# IO_Supply_Filter.net
KiCad netlist of a schematic drawn in Altium Designer
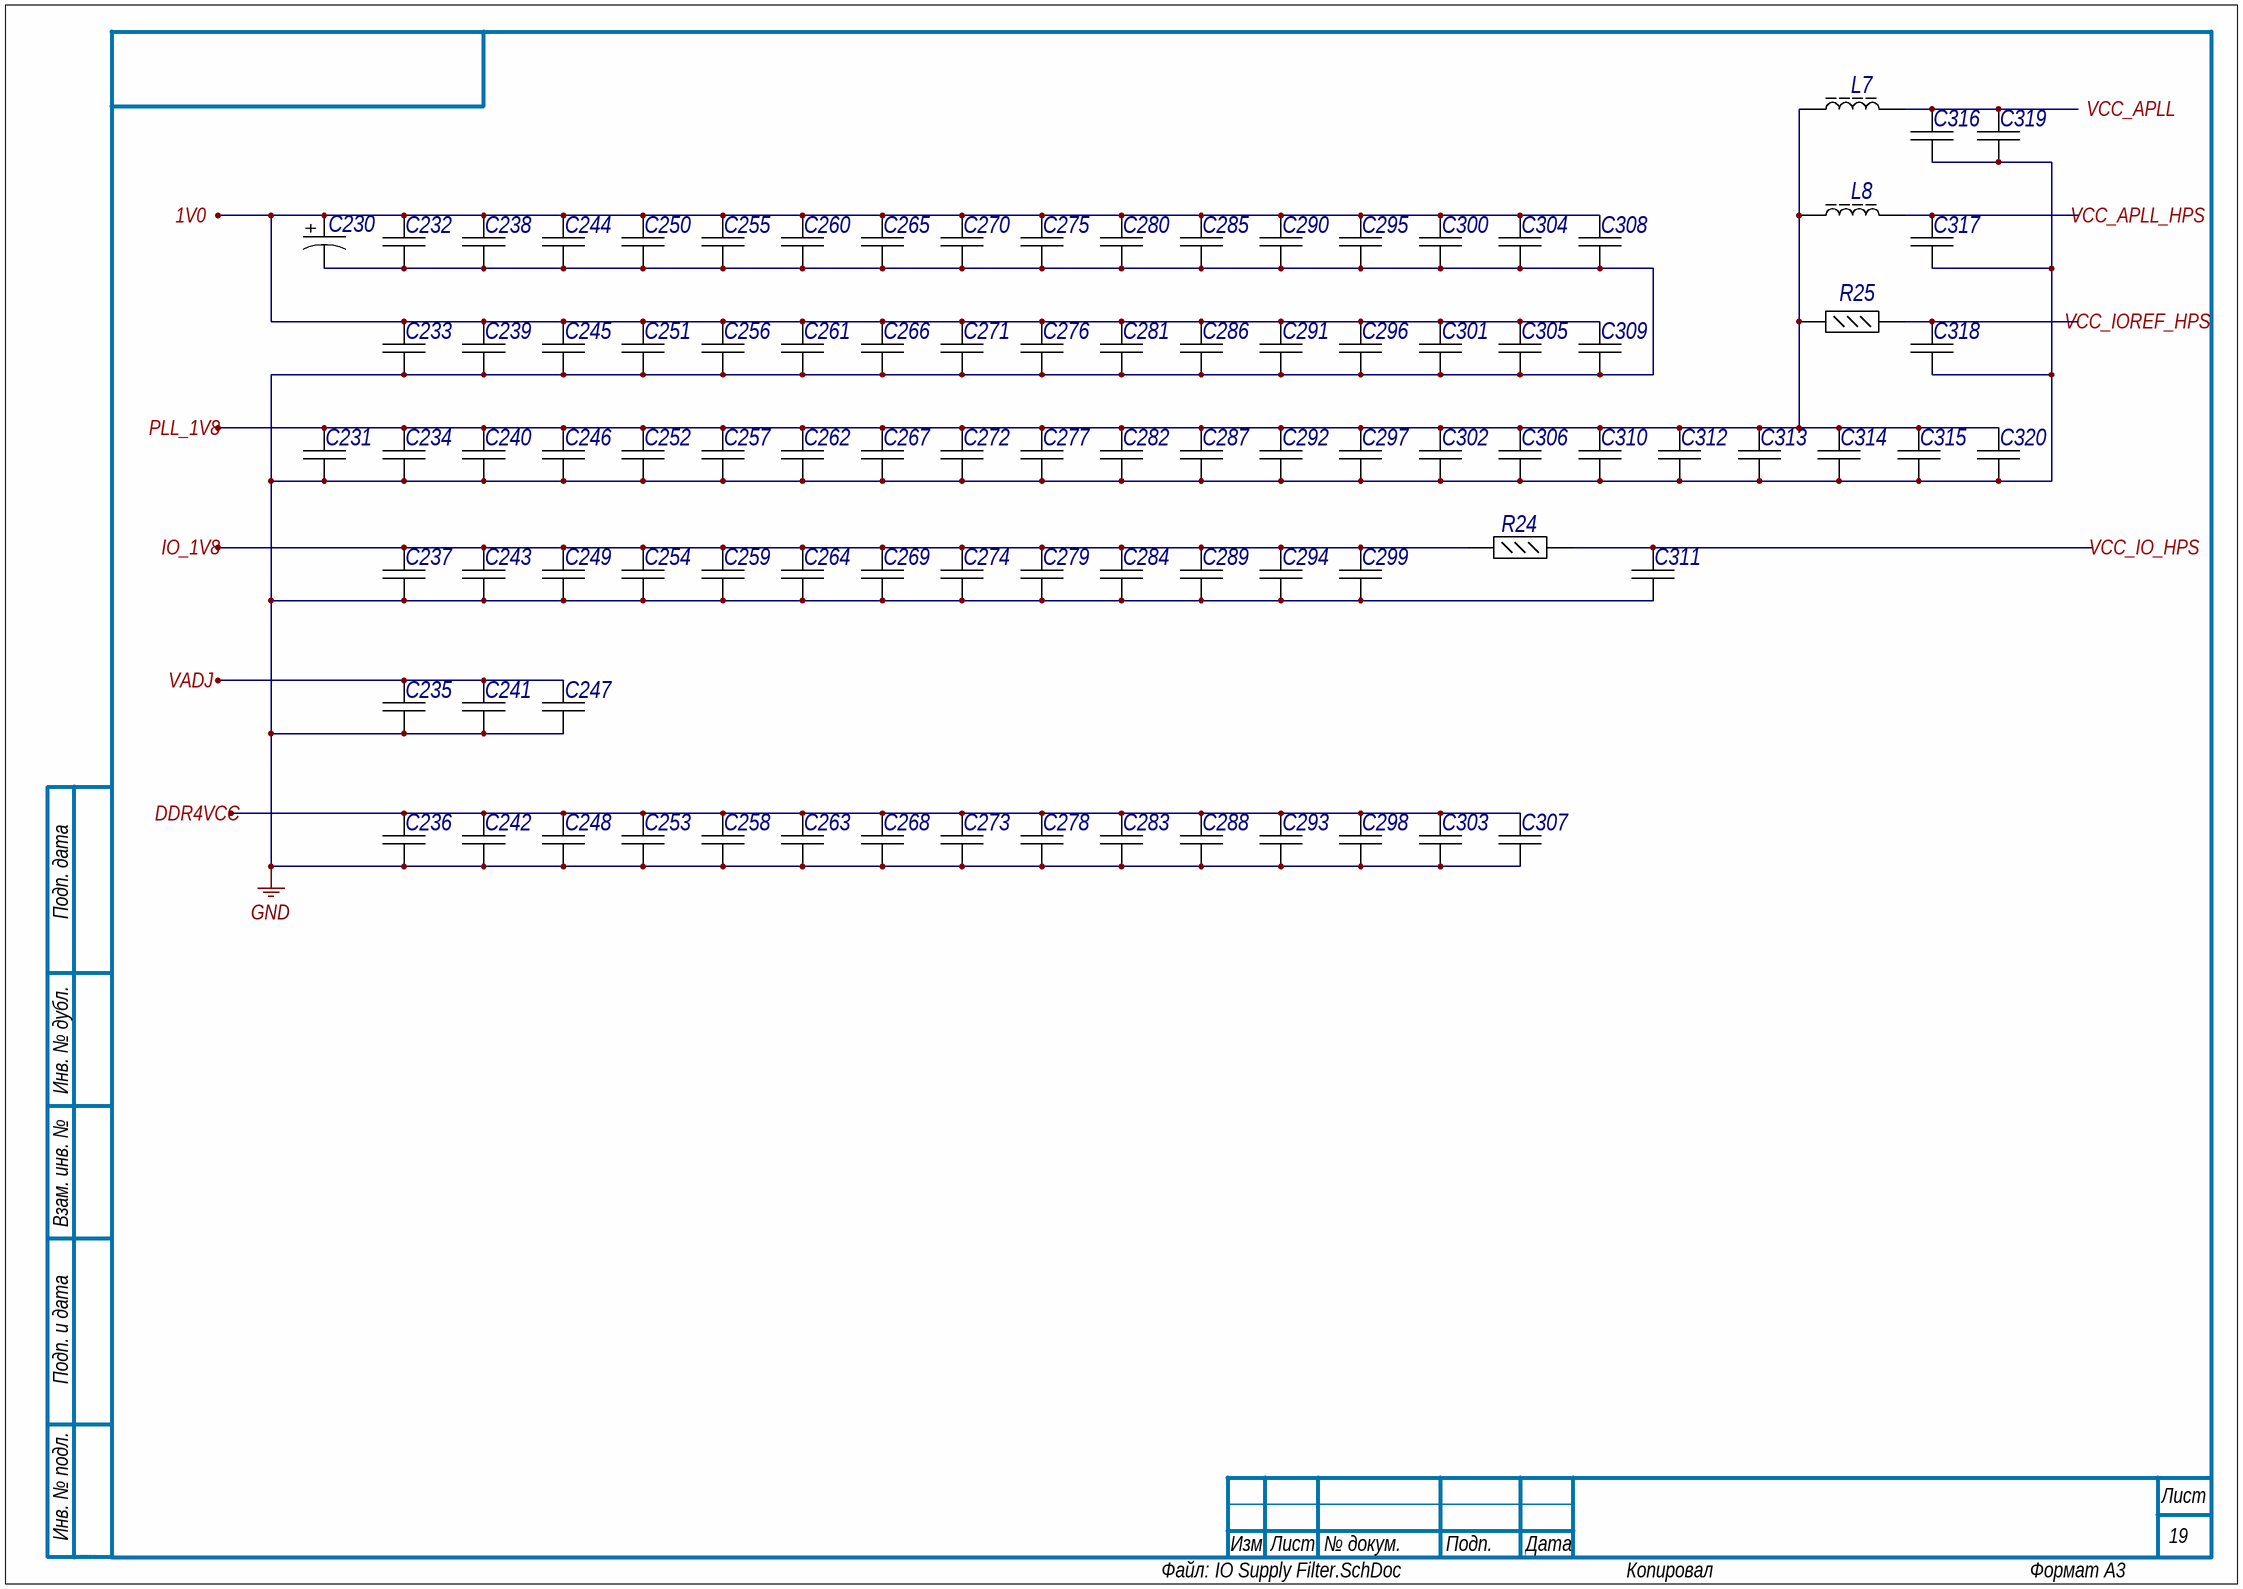
[diagram p0: IO Supply Filter.SchDoc]

(export (version "E")
  (design (tool "Eeschema 10.0.6"))
  (components
    (comp (ref "C230")
      (value "T520B337M2R5ATE045")
      (footprint "KEMT-520-B-2_M")
      (description "Tantalum Capacitor, 330 uF, +/- 20%, 2.5 V, -55 to 105 degC, 2-Pin Molded, RoHS, Tape and Reel")
      (libsource (lib "MiniPC DB") (part "CAP_P"))
    )
    (comp (ref "C231")
      (value "GRM31CR60J107ME39L")
      (footprint "CAPC3216X190X55ML30T25")
      (description "Chip Capacitor, 100 uF, +/- 20%, 6.3 V, -55 to 85 degC, 1206 (3216 Metric), RoHS, Tape and Reel")
      (fields (field (name "TOLERANCE") "20%"))
      (libsource (lib "MiniPC DB") (part "CAP_NP"))
    )
    (comp (ref "C232")
      (value "GRM033R60J104KE19D")
      (footprint "CAPC0603X33X15LL03T05")
      (description "Chip Capacitor, 100 nF, +/- 10%, 6.3 V, -55 to 85 degC, 0201 (0603 Metric), RoHS, Tape and Reel")
      (fields (field (name "TOLERANCE") "10%") (field (name "MANUFACTURER") "Basic Passives"))
      (libsource (lib "MiniPC DB") (part "CAP_NP"))
    )
    (comp (ref "C233")
      (value "GRM155R60J475ME87D")
      (footprint "CAPC1005X55X25LL05T10")
      (description "Chip Capacitor, 4.7 uF, +/- 20%, 6.3 V, -55 to 85 degC, 0402 (1005 Metric), RoHS, Tape and Reel")
      (fields (field (name "TOLERANCE") "20%") (field (name "MANUFACTURER") "Basic Passives"))
      (libsource (lib "MiniPC DB") (part "CAP_NP"))
    )
    (comp (ref "C234")
      (value "GRM033R60J104KE19D")
      (footprint "CAPC0603X33X15LL03T05")
      (description "Chip Capacitor, 100 nF, +/- 10%, 6.3 V, -55 to 85 degC, 0201 (0603 Metric), RoHS, Tape and Reel")
      (fields (field (name "TOLERANCE") "10%") (field (name "MANUFACTURER") "Basic Passives"))
      (libsource (lib "MiniPC DB") (part "CAP_NP"))
    )
    (comp (ref "C235")
      (value "GRM033R60J104KE19D")
      (footprint "CAPC0603X33X15LL03T05")
      (description "Chip Capacitor, 100 nF, +/- 10%, 6.3 V, -55 to 85 degC, 0201 (0603 Metric), RoHS, Tape and Reel")
      (fields (field (name "TOLERANCE") "10%") (field (name "MANUFACTURER") "Basic Passives"))
      (libsource (lib "MiniPC DB") (part "CAP_NP"))
    )
    (comp (ref "C236")
      (value "GRM033R60J104KE19D")
      (footprint "CAPC0603X33X15LL03T05")
      (description "Chip Capacitor, 100 nF, +/- 10%, 6.3 V, -55 to 85 degC, 0201 (0603 Metric), RoHS, Tape and Reel")
      (fields (field (name "TOLERANCE") "10%") (field (name "MANUFACTURER") "Basic Passives"))
      (libsource (lib "MiniPC DB") (part "CAP_NP"))
    )
    (comp (ref "C237")
      (value "GRM033R60J104KE19D")
      (footprint "CAPC0603X33X15LL03T05")
      (description "Chip Capacitor, 100 nF, +/- 10%, 6.3 V, -55 to 85 degC, 0201 (0603 Metric), RoHS, Tape and Reel")
      (fields (field (name "TOLERANCE") "10%") (field (name "MANUFACTURER") "Basic Passives"))
      (libsource (lib "MiniPC DB") (part "CAP_NP"))
    )
    (comp (ref "C238")
      (value "GRM033R60J104KE19D")
      (footprint "CAPC0603X33X15LL03T05")
      (description "Chip Capacitor, 100 nF, +/- 10%, 6.3 V, -55 to 85 degC, 0201 (0603 Metric), RoHS, Tape and Reel")
      (fields (field (name "TOLERANCE") "10%") (field (name "MANUFACTURER") "Basic Passives"))
      (libsource (lib "MiniPC DB") (part "CAP_NP"))
    )
    (comp (ref "C239")
      (value "GRM155R60J475ME87D")
      (footprint "CAPC1005X55X25LL05T10")
      (description "Chip Capacitor, 4.7 uF, +/- 20%, 6.3 V, -55 to 85 degC, 0402 (1005 Metric), RoHS, Tape and Reel")
      (fields (field (name "TOLERANCE") "20%") (field (name "MANUFACTURER") "Basic Passives"))
      (libsource (lib "MiniPC DB") (part "CAP_NP"))
    )
    (comp (ref "C240")
      (value "GRM033R60J104KE19D")
      (footprint "CAPC0603X33X15LL03T05")
      (description "Chip Capacitor, 100 nF, +/- 10%, 6.3 V, -55 to 85 degC, 0201 (0603 Metric), RoHS, Tape and Reel")
      (fields (field (name "TOLERANCE") "10%") (field (name "MANUFACTURER") "Basic Passives"))
      (libsource (lib "MiniPC DB") (part "CAP_NP"))
    )
    (comp (ref "C241")
      (value "GRM033R60J104KE19D")
      (footprint "CAPC0603X33X15LL03T05")
      (description "Chip Capacitor, 100 nF, +/- 10%, 6.3 V, -55 to 85 degC, 0201 (0603 Metric), RoHS, Tape and Reel")
      (fields (field (name "TOLERANCE") "10%") (field (name "MANUFACTURER") "Basic Passives"))
      (libsource (lib "MiniPC DB") (part "CAP_NP"))
    )
    (comp (ref "C242")
      (value "GRM033R60J104KE19D")
      (footprint "CAPC0603X33X15LL03T05")
      (description "Chip Capacitor, 100 nF, +/- 10%, 6.3 V, -55 to 85 degC, 0201 (0603 Metric), RoHS, Tape and Reel")
      (fields (field (name "TOLERANCE") "10%") (field (name "MANUFACTURER") "Basic Passives"))
      (libsource (lib "MiniPC DB") (part "CAP_NP"))
    )
    (comp (ref "C243")
      (value "GRM033R60J104KE19D")
      (footprint "CAPC0603X33X15LL03T05")
      (description "Chip Capacitor, 100 nF, +/- 10%, 6.3 V, -55 to 85 degC, 0201 (0603 Metric), RoHS, Tape and Reel")
      (fields (field (name "TOLERANCE") "10%") (field (name "MANUFACTURER") "Basic Passives"))
      (libsource (lib "MiniPC DB") (part "CAP_NP"))
    )
    (comp (ref "C244")
      (value "GRM033R60J104KE19D")
      (footprint "CAPC0603X33X15LL03T05")
      (description "Chip Capacitor, 100 nF, +/- 10%, 6.3 V, -55 to 85 degC, 0201 (0603 Metric), RoHS, Tape and Reel")
      (fields (field (name "TOLERANCE") "10%") (field (name "MANUFACTURER") "Basic Passives"))
      (libsource (lib "MiniPC DB") (part "CAP_NP"))
    )
    (comp (ref "C245")
      (value "GRM155R60J475ME87D")
      (footprint "CAPC1005X55X25LL05T10")
      (description "Chip Capacitor, 4.7 uF, +/- 20%, 6.3 V, -55 to 85 degC, 0402 (1005 Metric), RoHS, Tape and Reel")
      (fields (field (name "TOLERANCE") "20%") (field (name "MANUFACTURER") "Basic Passives"))
      (libsource (lib "MiniPC DB") (part "CAP_NP"))
    )
    (comp (ref "C246")
      (value "GRM033R60J104KE19D")
      (footprint "CAPC0603X33X15LL03T05")
      (description "Chip Capacitor, 100 nF, +/- 10%, 6.3 V, -55 to 85 degC, 0201 (0603 Metric), RoHS, Tape and Reel")
      (fields (field (name "TOLERANCE") "10%") (field (name "MANUFACTURER") "Basic Passives"))
      (libsource (lib "MiniPC DB") (part "CAP_NP"))
    )
    (comp (ref "C247")
      (value "GRM033R60J104KE19D")
      (footprint "CAPC0603X33X15LL03T05")
      (description "Chip Capacitor, 100 nF, +/- 10%, 6.3 V, -55 to 85 degC, 0201 (0603 Metric), RoHS, Tape and Reel")
      (fields (field (name "TOLERANCE") "10%") (field (name "MANUFACTURER") "Basic Passives"))
      (libsource (lib "MiniPC DB") (part "CAP_NP"))
    )
    (comp (ref "C248")
      (value "GRM033R60J104KE19D")
      (footprint "CAPC0603X33X15LL03T05")
      (description "Chip Capacitor, 100 nF, +/- 10%, 6.3 V, -55 to 85 degC, 0201 (0603 Metric), RoHS, Tape and Reel")
      (fields (field (name "TOLERANCE") "10%") (field (name "MANUFACTURER") "Basic Passives"))
      (libsource (lib "MiniPC DB") (part "CAP_NP"))
    )
    (comp (ref "C249")
      (value "GRM033R60J104KE19D")
      (footprint "CAPC0603X33X15LL03T05")
      (description "Chip Capacitor, 100 nF, +/- 10%, 6.3 V, -55 to 85 degC, 0201 (0603 Metric), RoHS, Tape and Reel")
      (fields (field (name "TOLERANCE") "10%") (field (name "MANUFACTURER") "Basic Passives"))
      (libsource (lib "MiniPC DB") (part "CAP_NP"))
    )
    (comp (ref "C250")
      (value "GRM033R60J104KE19D")
      (footprint "CAPC0603X33X15LL03T05")
      (description "Chip Capacitor, 100 nF, +/- 10%, 6.3 V, -55 to 85 degC, 0201 (0603 Metric), RoHS, Tape and Reel")
      (fields (field (name "TOLERANCE") "10%") (field (name "MANUFACTURER") "Basic Passives"))
      (libsource (lib "MiniPC DB") (part "CAP_NP"))
    )
    (comp (ref "C251")
      (value "GRM155R60J475ME87D")
      (footprint "CAPC1005X55X25LL05T10")
      (description "Chip Capacitor, 4.7 uF, +/- 20%, 6.3 V, -55 to 85 degC, 0402 (1005 Metric), RoHS, Tape and Reel")
      (fields (field (name "TOLERANCE") "20%") (field (name "MANUFACTURER") "Basic Passives"))
      (libsource (lib "MiniPC DB") (part "CAP_NP"))
    )
    (comp (ref "C252")
      (value "GRM033R60J104KE19D")
      (footprint "CAPC0603X33X15LL03T05")
      (description "Chip Capacitor, 100 nF, +/- 10%, 6.3 V, -55 to 85 degC, 0201 (0603 Metric), RoHS, Tape and Reel")
      (fields (field (name "TOLERANCE") "10%") (field (name "MANUFACTURER") "Basic Passives"))
      (libsource (lib "MiniPC DB") (part "CAP_NP"))
    )
    (comp (ref "C253")
      (value "GRM033R60J104KE19D")
      (footprint "CAPC0603X33X15LL03T05")
      (description "Chip Capacitor, 100 nF, +/- 10%, 6.3 V, -55 to 85 degC, 0201 (0603 Metric), RoHS, Tape and Reel")
      (fields (field (name "TOLERANCE") "10%") (field (name "MANUFACTURER") "Basic Passives"))
      (libsource (lib "MiniPC DB") (part "CAP_NP"))
    )
    (comp (ref "C254")
      (value "GRM033R60J104KE19D")
      (footprint "CAPC0603X33X15LL03T05")
      (description "Chip Capacitor, 100 nF, +/- 10%, 6.3 V, -55 to 85 degC, 0201 (0603 Metric), RoHS, Tape and Reel")
      (fields (field (name "TOLERANCE") "10%") (field (name "MANUFACTURER") "Basic Passives"))
      (libsource (lib "MiniPC DB") (part "CAP_NP"))
    )
    (comp (ref "C255")
      (value "GRM033R60J104KE19D")
      (footprint "CAPC0603X33X15LL03T05")
      (description "Chip Capacitor, 100 nF, +/- 10%, 6.3 V, -55 to 85 degC, 0201 (0603 Metric), RoHS, Tape and Reel")
      (fields (field (name "TOLERANCE") "10%") (field (name "MANUFACTURER") "Basic Passives"))
      (libsource (lib "MiniPC DB") (part "CAP_NP"))
    )
    (comp (ref "C256")
      (value "GRM155R60J475ME87D")
      (footprint "CAPC1005X55X25LL05T10")
      (description "Chip Capacitor, 4.7 uF, +/- 20%, 6.3 V, -55 to 85 degC, 0402 (1005 Metric), RoHS, Tape and Reel")
      (fields (field (name "TOLERANCE") "20%") (field (name "MANUFACTURER") "Basic Passives"))
      (libsource (lib "MiniPC DB") (part "CAP_NP"))
    )
    (comp (ref "C257")
      (value "GRM033R60J104KE19D")
      (footprint "CAPC0603X33X15LL03T05")
      (description "Chip Capacitor, 100 nF, +/- 10%, 6.3 V, -55 to 85 degC, 0201 (0603 Metric), RoHS, Tape and Reel")
      (fields (field (name "TOLERANCE") "10%") (field (name "MANUFACTURER") "Basic Passives"))
      (libsource (lib "MiniPC DB") (part "CAP_NP"))
    )
    (comp (ref "C258")
      (value "GRM033R60J104KE19D")
      (footprint "CAPC0603X33X15LL03T05")
      (description "Chip Capacitor, 100 nF, +/- 10%, 6.3 V, -55 to 85 degC, 0201 (0603 Metric), RoHS, Tape and Reel")
      (fields (field (name "TOLERANCE") "10%") (field (name "MANUFACTURER") "Basic Passives"))
      (libsource (lib "MiniPC DB") (part "CAP_NP"))
    )
    (comp (ref "C259")
      (value "GRM033R60J104KE19D")
      (footprint "CAPC0603X33X15LL03T05")
      (description "Chip Capacitor, 100 nF, +/- 10%, 6.3 V, -55 to 85 degC, 0201 (0603 Metric), RoHS, Tape and Reel")
      (fields (field (name "TOLERANCE") "10%") (field (name "MANUFACTURER") "Basic Passives"))
      (libsource (lib "MiniPC DB") (part "CAP_NP"))
    )
    (comp (ref "C260")
      (value "GRM033R60J104KE19D")
      (footprint "CAPC0603X33X15LL03T05")
      (description "Chip Capacitor, 100 nF, +/- 10%, 6.3 V, -55 to 85 degC, 0201 (0603 Metric), RoHS, Tape and Reel")
      (fields (field (name "TOLERANCE") "10%") (field (name "MANUFACTURER") "Basic Passives"))
      (libsource (lib "MiniPC DB") (part "CAP_NP"))
    )
    (comp (ref "C261")
      (value "GRM155R60J475ME87D")
      (footprint "CAPC1005X55X25LL05T10")
      (description "Chip Capacitor, 4.7 uF, +/- 20%, 6.3 V, -55 to 85 degC, 0402 (1005 Metric), RoHS, Tape and Reel")
      (fields (field (name "TOLERANCE") "20%") (field (name "MANUFACTURER") "Basic Passives"))
      (libsource (lib "MiniPC DB") (part "CAP_NP"))
    )
    (comp (ref "C262")
      (value "GRM033R60J104KE19D")
      (footprint "CAPC0603X33X15LL03T05")
      (description "Chip Capacitor, 100 nF, +/- 10%, 6.3 V, -55 to 85 degC, 0201 (0603 Metric), RoHS, Tape and Reel")
      (fields (field (name "TOLERANCE") "10%") (field (name "MANUFACTURER") "Basic Passives"))
      (libsource (lib "MiniPC DB") (part "CAP_NP"))
    )
    (comp (ref "C263")
      (value "GRM033R60J104KE19D")
      (footprint "CAPC0603X33X15LL03T05")
      (description "Chip Capacitor, 100 nF, +/- 10%, 6.3 V, -55 to 85 degC, 0201 (0603 Metric), RoHS, Tape and Reel")
      (fields (field (name "TOLERANCE") "10%") (field (name "MANUFACTURER") "Basic Passives"))
      (libsource (lib "MiniPC DB") (part "CAP_NP"))
    )
    (comp (ref "C264")
      (value "GRM033R60J104KE19D")
      (footprint "CAPC0603X33X15LL03T05")
      (description "Chip Capacitor, 100 nF, +/- 10%, 6.3 V, -55 to 85 degC, 0201 (0603 Metric), RoHS, Tape and Reel")
      (fields (field (name "TOLERANCE") "10%") (field (name "MANUFACTURER") "Basic Passives"))
      (libsource (lib "MiniPC DB") (part "CAP_NP"))
    )
    (comp (ref "C265")
      (value "GRM033R60J104KE19D")
      (footprint "CAPC0603X33X15LL03T05")
      (description "Chip Capacitor, 100 nF, +/- 10%, 6.3 V, -55 to 85 degC, 0201 (0603 Metric), RoHS, Tape and Reel")
      (fields (field (name "TOLERANCE") "10%") (field (name "MANUFACTURER") "Basic Passives"))
      (libsource (lib "MiniPC DB") (part "CAP_NP"))
    )
    (comp (ref "C266")
      (value "GRM155R60J475ME87D")
      (footprint "CAPC1005X55X25LL05T10")
      (description "Chip Capacitor, 4.7 uF, +/- 20%, 6.3 V, -55 to 85 degC, 0402 (1005 Metric), RoHS, Tape and Reel")
      (fields (field (name "TOLERANCE") "20%") (field (name "MANUFACTURER") "Basic Passives"))
      (libsource (lib "MiniPC DB") (part "CAP_NP"))
    )
    (comp (ref "C267")
      (value "GRM033R60J104KE19D")
      (footprint "CAPC0603X33X15LL03T05")
      (description "Chip Capacitor, 100 nF, +/- 10%, 6.3 V, -55 to 85 degC, 0201 (0603 Metric), RoHS, Tape and Reel")
      (fields (field (name "TOLERANCE") "10%") (field (name "MANUFACTURER") "Basic Passives"))
      (libsource (lib "MiniPC DB") (part "CAP_NP"))
    )
    (comp (ref "C268")
      (value "GRM033R60J104KE19D")
      (footprint "CAPC0603X33X15LL03T05")
      (description "Chip Capacitor, 100 nF, +/- 10%, 6.3 V, -55 to 85 degC, 0201 (0603 Metric), RoHS, Tape and Reel")
      (fields (field (name "TOLERANCE") "10%") (field (name "MANUFACTURER") "Basic Passives"))
      (libsource (lib "MiniPC DB") (part "CAP_NP"))
    )
    (comp (ref "C269")
      (value "GRM033R60J104KE19D")
      (footprint "CAPC0603X33X15LL03T05")
      (description "Chip Capacitor, 100 nF, +/- 10%, 6.3 V, -55 to 85 degC, 0201 (0603 Metric), RoHS, Tape and Reel")
      (fields (field (name "TOLERANCE") "10%") (field (name "MANUFACTURER") "Basic Passives"))
      (libsource (lib "MiniPC DB") (part "CAP_NP"))
    )
    (comp (ref "C270")
      (value "GRM033R60J104KE19D")
      (footprint "CAPC0603X33X15LL03T05")
      (description "Chip Capacitor, 100 nF, +/- 10%, 6.3 V, -55 to 85 degC, 0201 (0603 Metric), RoHS, Tape and Reel")
      (fields (field (name "TOLERANCE") "10%") (field (name "MANUFACTURER") "Basic Passives"))
      (libsource (lib "MiniPC DB") (part "CAP_NP"))
    )
    (comp (ref "C271")
      (value "GRM155R60J475ME87D")
      (footprint "CAPC1005X55X25LL05T10")
      (description "Chip Capacitor, 4.7 uF, +/- 20%, 6.3 V, -55 to 85 degC, 0402 (1005 Metric), RoHS, Tape and Reel")
      (fields (field (name "TOLERANCE") "20%") (field (name "MANUFACTURER") "Basic Passives"))
      (libsource (lib "MiniPC DB") (part "CAP_NP"))
    )
    (comp (ref "C272")
      (value "GRM033R60J104KE19D")
      (footprint "CAPC0603X33X15LL03T05")
      (description "Chip Capacitor, 100 nF, +/- 10%, 6.3 V, -55 to 85 degC, 0201 (0603 Metric), RoHS, Tape and Reel")
      (fields (field (name "TOLERANCE") "10%") (field (name "MANUFACTURER") "Basic Passives"))
      (libsource (lib "MiniPC DB") (part "CAP_NP"))
    )
    (comp (ref "C273")
      (value "GRM033R60J104KE19D")
      (footprint "CAPC0603X33X15LL03T05")
      (description "Chip Capacitor, 100 nF, +/- 10%, 6.3 V, -55 to 85 degC, 0201 (0603 Metric), RoHS, Tape and Reel")
      (fields (field (name "TOLERANCE") "10%") (field (name "MANUFACTURER") "Basic Passives"))
      (libsource (lib "MiniPC DB") (part "CAP_NP"))
    )
    (comp (ref "C274")
      (value "GRM033R60J104KE19D")
      (footprint "CAPC0603X33X15LL03T05")
      (description "Chip Capacitor, 100 nF, +/- 10%, 6.3 V, -55 to 85 degC, 0201 (0603 Metric), RoHS, Tape and Reel")
      (fields (field (name "TOLERANCE") "10%") (field (name "MANUFACTURER") "Basic Passives"))
      (libsource (lib "MiniPC DB") (part "CAP_NP"))
    )
    (comp (ref "C275")
      (value "GRM033R60J104KE19D")
      (footprint "CAPC0603X33X15LL03T05")
      (description "Chip Capacitor, 100 nF, +/- 10%, 6.3 V, -55 to 85 degC, 0201 (0603 Metric), RoHS, Tape and Reel")
      (fields (field (name "TOLERANCE") "10%") (field (name "MANUFACTURER") "Basic Passives"))
      (libsource (lib "MiniPC DB") (part "CAP_NP"))
    )
    (comp (ref "C276")
      (value "GRM155R60J475ME87D")
      (footprint "CAPC1005X55X25LL05T10")
      (description "Chip Capacitor, 4.7 uF, +/- 20%, 6.3 V, -55 to 85 degC, 0402 (1005 Metric), RoHS, Tape and Reel")
      (fields (field (name "TOLERANCE") "20%") (field (name "MANUFACTURER") "Basic Passives"))
      (libsource (lib "MiniPC DB") (part "CAP_NP"))
    )
    (comp (ref "C277")
      (value "GRM033R60J104KE19D")
      (footprint "CAPC0603X33X15LL03T05")
      (description "Chip Capacitor, 100 nF, +/- 10%, 6.3 V, -55 to 85 degC, 0201 (0603 Metric), RoHS, Tape and Reel")
      (fields (field (name "TOLERANCE") "10%") (field (name "MANUFACTURER") "Basic Passives"))
      (libsource (lib "MiniPC DB") (part "CAP_NP"))
    )
    (comp (ref "C278")
      (value "GRM033R60J104KE19D")
      (footprint "CAPC0603X33X15LL03T05")
      (description "Chip Capacitor, 100 nF, +/- 10%, 6.3 V, -55 to 85 degC, 0201 (0603 Metric), RoHS, Tape and Reel")
      (fields (field (name "TOLERANCE") "10%") (field (name "MANUFACTURER") "Basic Passives"))
      (libsource (lib "MiniPC DB") (part "CAP_NP"))
    )
    (comp (ref "C279")
      (value "GRM033R60J104KE19D")
      (footprint "CAPC0603X33X15LL03T05")
      (description "Chip Capacitor, 100 nF, +/- 10%, 6.3 V, -55 to 85 degC, 0201 (0603 Metric), RoHS, Tape and Reel")
      (fields (field (name "TOLERANCE") "10%") (field (name "MANUFACTURER") "Basic Passives"))
      (libsource (lib "MiniPC DB") (part "CAP_NP"))
    )
    (comp (ref "C280")
      (value "GRM033R60J104KE19D")
      (footprint "CAPC0603X33X15LL03T05")
      (description "Chip Capacitor, 100 nF, +/- 10%, 6.3 V, -55 to 85 degC, 0201 (0603 Metric), RoHS, Tape and Reel")
      (fields (field (name "TOLERANCE") "10%") (field (name "MANUFACTURER") "Basic Passives"))
      (libsource (lib "MiniPC DB") (part "CAP_NP"))
    )
    (comp (ref "C281")
      (value "GRM155R60J475ME87D")
      (footprint "CAPC1005X55X25LL05T10")
      (description "Chip Capacitor, 4.7 uF, +/- 20%, 6.3 V, -55 to 85 degC, 0402 (1005 Metric), RoHS, Tape and Reel")
      (fields (field (name "TOLERANCE") "20%") (field (name "MANUFACTURER") "Basic Passives"))
      (libsource (lib "MiniPC DB") (part "CAP_NP"))
    )
    (comp (ref "C282")
      (value "GRM033R60J104KE19D")
      (footprint "CAPC0603X33X15LL03T05")
      (description "Chip Capacitor, 100 nF, +/- 10%, 6.3 V, -55 to 85 degC, 0201 (0603 Metric), RoHS, Tape and Reel")
      (fields (field (name "TOLERANCE") "10%") (field (name "MANUFACTURER") "Basic Passives"))
      (libsource (lib "MiniPC DB") (part "CAP_NP"))
    )
    (comp (ref "C283")
      (value "GRM033R60J104KE19D")
      (footprint "CAPC0603X33X15LL03T05")
      (description "Chip Capacitor, 100 nF, +/- 10%, 6.3 V, -55 to 85 degC, 0201 (0603 Metric), RoHS, Tape and Reel")
      (fields (field (name "TOLERANCE") "10%") (field (name "MANUFACTURER") "Basic Passives"))
      (libsource (lib "MiniPC DB") (part "CAP_NP"))
    )
    (comp (ref "C284")
      (value "GRM033R60J104KE19D")
      (footprint "CAPC0603X33X15LL03T05")
      (description "Chip Capacitor, 100 nF, +/- 10%, 6.3 V, -55 to 85 degC, 0201 (0603 Metric), RoHS, Tape and Reel")
      (fields (field (name "TOLERANCE") "10%") (field (name "MANUFACTURER") "Basic Passives"))
      (libsource (lib "MiniPC DB") (part "CAP_NP"))
    )
    (comp (ref "C285")
      (value "GRM033R60J104KE19D")
      (footprint "CAPC0603X33X15LL03T05")
      (description "Chip Capacitor, 100 nF, +/- 10%, 6.3 V, -55 to 85 degC, 0201 (0603 Metric), RoHS, Tape and Reel")
      (fields (field (name "TOLERANCE") "10%") (field (name "MANUFACTURER") "Basic Passives"))
      (libsource (lib "MiniPC DB") (part "CAP_NP"))
    )
    (comp (ref "C286")
      (value "GRM155R60J475ME87D")
      (footprint "CAPC1005X55X25LL05T10")
      (description "Chip Capacitor, 4.7 uF, +/- 20%, 6.3 V, -55 to 85 degC, 0402 (1005 Metric), RoHS, Tape and Reel")
      (fields (field (name "TOLERANCE") "20%") (field (name "MANUFACTURER") "Basic Passives"))
      (libsource (lib "MiniPC DB") (part "CAP_NP"))
    )
    (comp (ref "C287")
      (value "GRM033R60J104KE19D")
      (footprint "CAPC0603X33X15LL03T05")
      (description "Chip Capacitor, 100 nF, +/- 10%, 6.3 V, -55 to 85 degC, 0201 (0603 Metric), RoHS, Tape and Reel")
      (fields (field (name "TOLERANCE") "10%") (field (name "MANUFACTURER") "Basic Passives"))
      (libsource (lib "MiniPC DB") (part "CAP_NP"))
    )
    (comp (ref "C288")
      (value "GRM033R60J104KE19D")
      (footprint "CAPC0603X33X15LL03T05")
      (description "Chip Capacitor, 100 nF, +/- 10%, 6.3 V, -55 to 85 degC, 0201 (0603 Metric), RoHS, Tape and Reel")
      (fields (field (name "TOLERANCE") "10%") (field (name "MANUFACTURER") "Basic Passives"))
      (libsource (lib "MiniPC DB") (part "CAP_NP"))
    )
    (comp (ref "C289")
      (value "GRM033R60J104KE19D")
      (footprint "CAPC0603X33X15LL03T05")
      (description "Chip Capacitor, 100 nF, +/- 10%, 6.3 V, -55 to 85 degC, 0201 (0603 Metric), RoHS, Tape and Reel")
      (fields (field (name "TOLERANCE") "10%") (field (name "MANUFACTURER") "Basic Passives"))
      (libsource (lib "MiniPC DB") (part "CAP_NP"))
    )
    (comp (ref "C290")
      (value "GRM033R60J104KE19D")
      (footprint "CAPC0603X33X15LL03T05")
      (description "Chip Capacitor, 100 nF, +/- 10%, 6.3 V, -55 to 85 degC, 0201 (0603 Metric), RoHS, Tape and Reel")
      (fields (field (name "TOLERANCE") "10%") (field (name "MANUFACTURER") "Basic Passives"))
      (libsource (lib "MiniPC DB") (part "CAP_NP"))
    )
    (comp (ref "C291")
      (value "GRM155R60J475ME87D")
      (footprint "CAPC1005X55X25LL05T10")
      (description "Chip Capacitor, 4.7 uF, +/- 20%, 6.3 V, -55 to 85 degC, 0402 (1005 Metric), RoHS, Tape and Reel")
      (fields (field (name "TOLERANCE") "20%") (field (name "MANUFACTURER") "Basic Passives"))
      (libsource (lib "MiniPC DB") (part "CAP_NP"))
    )
    (comp (ref "C292")
      (value "GRM033R60J104KE19D")
      (footprint "CAPC0603X33X15LL03T05")
      (description "Chip Capacitor, 100 nF, +/- 10%, 6.3 V, -55 to 85 degC, 0201 (0603 Metric), RoHS, Tape and Reel")
      (fields (field (name "TOLERANCE") "10%") (field (name "MANUFACTURER") "Basic Passives"))
      (libsource (lib "MiniPC DB") (part "CAP_NP"))
    )
    (comp (ref "C293")
      (value "GRM033R60J104KE19D")
      (footprint "CAPC0603X33X15LL03T05")
      (description "Chip Capacitor, 100 nF, +/- 10%, 6.3 V, -55 to 85 degC, 0201 (0603 Metric), RoHS, Tape and Reel")
      (fields (field (name "TOLERANCE") "10%") (field (name "MANUFACTURER") "Basic Passives"))
      (libsource (lib "MiniPC DB") (part "CAP_NP"))
    )
    (comp (ref "C294")
      (value "GRM033R60J104KE19D")
      (footprint "CAPC0603X33X15LL03T05")
      (description "Chip Capacitor, 100 nF, +/- 10%, 6.3 V, -55 to 85 degC, 0201 (0603 Metric), RoHS, Tape and Reel")
      (fields (field (name "TOLERANCE") "10%") (field (name "MANUFACTURER") "Basic Passives"))
      (libsource (lib "MiniPC DB") (part "CAP_NP"))
    )
    (comp (ref "C295")
      (value "GRM033R60J104KE19D")
      (footprint "CAPC0603X33X15LL03T05")
      (description "Chip Capacitor, 100 nF, +/- 10%, 6.3 V, -55 to 85 degC, 0201 (0603 Metric), RoHS, Tape and Reel")
      (fields (field (name "TOLERANCE") "10%") (field (name "MANUFACTURER") "Basic Passives"))
      (libsource (lib "MiniPC DB") (part "CAP_NP"))
    )
    (comp (ref "C296")
      (value "GRM155R60J475ME87D")
      (footprint "CAPC1005X55X25LL05T10")
      (description "Chip Capacitor, 4.7 uF, +/- 20%, 6.3 V, -55 to 85 degC, 0402 (1005 Metric), RoHS, Tape and Reel")
      (fields (field (name "TOLERANCE") "20%") (field (name "MANUFACTURER") "Basic Passives"))
      (libsource (lib "MiniPC DB") (part "CAP_NP"))
    )
    (comp (ref "C297")
      (value "GRM033R60J104KE19D")
      (footprint "CAPC0603X33X15LL03T05")
      (description "Chip Capacitor, 100 nF, +/- 10%, 6.3 V, -55 to 85 degC, 0201 (0603 Metric), RoHS, Tape and Reel")
      (fields (field (name "TOLERANCE") "10%") (field (name "MANUFACTURER") "Basic Passives"))
      (libsource (lib "MiniPC DB") (part "CAP_NP"))
    )
    (comp (ref "C298")
      (value "GRM033R60J104KE19D")
      (footprint "CAPC0603X33X15LL03T05")
      (description "Chip Capacitor, 100 nF, +/- 10%, 6.3 V, -55 to 85 degC, 0201 (0603 Metric), RoHS, Tape and Reel")
      (fields (field (name "TOLERANCE") "10%") (field (name "MANUFACTURER") "Basic Passives"))
      (libsource (lib "MiniPC DB") (part "CAP_NP"))
    )
    (comp (ref "C299")
      (value "GRM033R60J104KE19D")
      (footprint "CAPC0603X33X15LL03T05")
      (description "Chip Capacitor, 100 nF, +/- 10%, 6.3 V, -55 to 85 degC, 0201 (0603 Metric), RoHS, Tape and Reel")
      (fields (field (name "TOLERANCE") "10%") (field (name "MANUFACTURER") "Basic Passives"))
      (libsource (lib "MiniPC DB") (part "CAP_NP"))
    )
    (comp (ref "C300")
      (value "GRM033R60J104KE19D")
      (footprint "CAPC0603X33X15LL03T05")
      (description "Chip Capacitor, 100 nF, +/- 10%, 6.3 V, -55 to 85 degC, 0201 (0603 Metric), RoHS, Tape and Reel")
      (fields (field (name "TOLERANCE") "10%") (field (name "MANUFACTURER") "Basic Passives"))
      (libsource (lib "MiniPC DB") (part "CAP_NP"))
    )
    (comp (ref "C301")
      (value "GRM155R60J475ME87D")
      (footprint "CAPC1005X55X25LL05T10")
      (description "Chip Capacitor, 4.7 uF, +/- 20%, 6.3 V, -55 to 85 degC, 0402 (1005 Metric), RoHS, Tape and Reel")
      (fields (field (name "TOLERANCE") "20%") (field (name "MANUFACTURER") "Basic Passives"))
      (libsource (lib "MiniPC DB") (part "CAP_NP"))
    )
    (comp (ref "C302")
      (value "GRM033R60J104KE19D")
      (footprint "CAPC0603X33X15LL03T05")
      (description "Chip Capacitor, 100 nF, +/- 10%, 6.3 V, -55 to 85 degC, 0201 (0603 Metric), RoHS, Tape and Reel")
      (fields (field (name "TOLERANCE") "10%") (field (name "MANUFACTURER") "Basic Passives"))
      (libsource (lib "MiniPC DB") (part "CAP_NP"))
    )
    (comp (ref "C303")
      (value "GRM033R60J104KE19D")
      (footprint "CAPC0603X33X15LL03T05")
      (description "Chip Capacitor, 100 nF, +/- 10%, 6.3 V, -55 to 85 degC, 0201 (0603 Metric), RoHS, Tape and Reel")
      (fields (field (name "TOLERANCE") "10%") (field (name "MANUFACTURER") "Basic Passives"))
      (libsource (lib "MiniPC DB") (part "CAP_NP"))
    )
    (comp (ref "C304")
      (value "GRM033R60J104KE19D")
      (footprint "CAPC0603X33X15LL03T05")
      (description "Chip Capacitor, 100 nF, +/- 10%, 6.3 V, -55 to 85 degC, 0201 (0603 Metric), RoHS, Tape and Reel")
      (fields (field (name "TOLERANCE") "10%") (field (name "MANUFACTURER") "Basic Passives"))
      (libsource (lib "MiniPC DB") (part "CAP_NP"))
    )
    (comp (ref "C305")
      (value "GRM155R60J475ME87D")
      (footprint "CAPC1005X55X25LL05T10")
      (description "Chip Capacitor, 4.7 uF, +/- 20%, 6.3 V, -55 to 85 degC, 0402 (1005 Metric), RoHS, Tape and Reel")
      (fields (field (name "TOLERANCE") "20%") (field (name "MANUFACTURER") "Basic Passives"))
      (libsource (lib "MiniPC DB") (part "CAP_NP"))
    )
    (comp (ref "C306")
      (value "GRM033R60J104KE19D")
      (footprint "CAPC0603X33X15LL03T05")
      (description "Chip Capacitor, 100 nF, +/- 10%, 6.3 V, -55 to 85 degC, 0201 (0603 Metric), RoHS, Tape and Reel")
      (fields (field (name "TOLERANCE") "10%") (field (name "MANUFACTURER") "Basic Passives"))
      (libsource (lib "MiniPC DB") (part "CAP_NP"))
    )
    (comp (ref "C307")
      (value "GRM033R60J104KE19D")
      (footprint "CAPC0603X33X15LL03T05")
      (description "Chip Capacitor, 100 nF, +/- 10%, 6.3 V, -55 to 85 degC, 0201 (0603 Metric), RoHS, Tape and Reel")
      (fields (field (name "TOLERANCE") "10%") (field (name "MANUFACTURER") "Basic Passives"))
      (libsource (lib "MiniPC DB") (part "CAP_NP"))
    )
    (comp (ref "C308")
      (value "GRM033R60J104KE19D")
      (footprint "CAPC0603X33X15LL03T05")
      (description "Chip Capacitor, 100 nF, +/- 10%, 6.3 V, -55 to 85 degC, 0201 (0603 Metric), RoHS, Tape and Reel")
      (fields (field (name "TOLERANCE") "10%") (field (name "MANUFACTURER") "Basic Passives"))
      (libsource (lib "MiniPC DB") (part "CAP_NP"))
    )
    (comp (ref "C309")
      (value "GRM155R60J475ME87D")
      (footprint "CAPC1005X55X25LL05T10")
      (description "Chip Capacitor, 4.7 uF, +/- 20%, 6.3 V, -55 to 85 degC, 0402 (1005 Metric), RoHS, Tape and Reel")
      (fields (field (name "TOLERANCE") "20%") (field (name "MANUFACTURER") "Basic Passives"))
      (libsource (lib "MiniPC DB") (part "CAP_NP"))
    )
    (comp (ref "C310")
      (value "GRM033R60J104KE19D")
      (footprint "CAPC0603X33X15LL03T05")
      (description "Chip Capacitor, 100 nF, +/- 10%, 6.3 V, -55 to 85 degC, 0201 (0603 Metric), RoHS, Tape and Reel")
      (fields (field (name "TOLERANCE") "10%") (field (name "MANUFACTURER") "Basic Passives"))
      (libsource (lib "MiniPC DB") (part "CAP_NP"))
    )
    (comp (ref "C311")
      (value "GRM033R60J104KE19D")
      (footprint "CAPC0603X33X15LL03T05")
      (description "Chip Capacitor, 100 nF, +/- 10%, 6.3 V, -55 to 85 degC, 0201 (0603 Metric), RoHS, Tape and Reel")
      (fields (field (name "TOLERANCE") "10%") (field (name "MANUFACTURER") "Basic Passives"))
      (libsource (lib "MiniPC DB") (part "CAP_NP"))
    )
    (comp (ref "C312")
      (value "GRM033R60J104KE19D")
      (footprint "CAPC0603X33X15LL03T05")
      (description "Chip Capacitor, 100 nF, +/- 10%, 6.3 V, -55 to 85 degC, 0201 (0603 Metric), RoHS, Tape and Reel")
      (fields (field (name "TOLERANCE") "10%") (field (name "MANUFACTURER") "Basic Passives"))
      (libsource (lib "MiniPC DB") (part "CAP_NP"))
    )
    (comp (ref "C313")
      (value "GRM033R60J104KE19D")
      (footprint "CAPC0603X33X15LL03T05")
      (description "Chip Capacitor, 100 nF, +/- 10%, 6.3 V, -55 to 85 degC, 0201 (0603 Metric), RoHS, Tape and Reel")
      (fields (field (name "TOLERANCE") "10%") (field (name "MANUFACTURER") "Basic Passives"))
      (libsource (lib "MiniPC DB") (part "CAP_NP"))
    )
    (comp (ref "C314")
      (value "GRM033R60J104KE19D")
      (footprint "CAPC0603X33X15LL03T05")
      (description "Chip Capacitor, 100 nF, +/- 10%, 6.3 V, -55 to 85 degC, 0201 (0603 Metric), RoHS, Tape and Reel")
      (fields (field (name "TOLERANCE") "10%") (field (name "MANUFACTURER") "Basic Passives"))
      (libsource (lib "MiniPC DB") (part "CAP_NP"))
    )
    (comp (ref "C315")
      (value "GRM033R60J104KE19D")
      (footprint "CAPC0603X33X15LL03T05")
      (description "Chip Capacitor, 100 nF, +/- 10%, 6.3 V, -55 to 85 degC, 0201 (0603 Metric), RoHS, Tape and Reel")
      (fields (field (name "TOLERANCE") "10%") (field (name "MANUFACTURER") "Basic Passives"))
      (libsource (lib "MiniPC DB") (part "CAP_NP"))
    )
    (comp (ref "C316")
      (value "GRM033R60J104KE19D")
      (footprint "CAPC0603X33X15LL03T05")
      (description "Chip Capacitor, 100 nF, +/- 10%, 6.3 V, -55 to 85 degC, 0201 (0603 Metric), RoHS, Tape and Reel")
      (fields (field (name "TOLERANCE") "10%") (field (name "MANUFACTURER") "Basic Passives"))
      (libsource (lib "MiniPC DB") (part "CAP_NP"))
    )
    (comp (ref "C317")
      (value "GRM033R60J104KE19D")
      (footprint "CAPC0603X33X15LL03T05")
      (description "Chip Capacitor, 100 nF, +/- 10%, 6.3 V, -55 to 85 degC, 0201 (0603 Metric), RoHS, Tape and Reel")
      (fields (field (name "TOLERANCE") "10%") (field (name "MANUFACTURER") "Basic Passives"))
      (libsource (lib "MiniPC DB") (part "CAP_NP"))
    )
    (comp (ref "C318")
      (value "GRM033R60J104KE19D")
      (footprint "CAPC0603X33X15LL03T05")
      (description "Chip Capacitor, 100 nF, +/- 10%, 6.3 V, -55 to 85 degC, 0201 (0603 Metric), RoHS, Tape and Reel")
      (fields (field (name "TOLERANCE") "10%") (field (name "MANUFACTURER") "Basic Passives"))
      (libsource (lib "MiniPC DB") (part "CAP_NP"))
    )
    (comp (ref "C319")
      (value "GRM033R60J104KE19D")
      (footprint "CAPC0603X33X15LL03T05")
      (description "Chip Capacitor, 100 nF, +/- 10%, 6.3 V, -55 to 85 degC, 0201 (0603 Metric), RoHS, Tape and Reel")
      (fields (field (name "TOLERANCE") "10%") (field (name "MANUFACTURER") "Basic Passives"))
      (libsource (lib "MiniPC DB") (part "CAP_NP"))
    )
    (comp (ref "C320")
      (value "GRM033R60J104KE19D")
      (footprint "CAPC0603X33X15LL03T05")
      (description "Chip Capacitor, 100 nF, +/- 10%, 6.3 V, -55 to 85 degC, 0201 (0603 Metric), RoHS, Tape and Reel")
      (fields (field (name "TOLERANCE") "10%") (field (name "MANUFACTURER") "Basic Passives"))
      (libsource (lib "MiniPC DB") (part "CAP_NP"))
    )
    (comp (ref "L7")
      (value "742792609")
      (footprint "SMD-0603")
      (description "SMD EMI Suppression Ferrite Bead WE-CBF, Z = 30 Ohm")
      (libsource (lib "MiniPC DB") (part "Choke"))
    )
    (comp (ref "L8")
      (value "742792609")
      (footprint "SMD-0603")
      (description "SMD EMI Suppression Ferrite Bead WE-CBF, Z = 30 Ohm")
      (libsource (lib "MiniPC DB") (part "Choke"))
    )
    (comp (ref "R24")
      (value "ERJ-2GE0R00X")
      (footprint "RESC1005X40X25LL05T05")
      (description "Chip Resistor, 0 mOhm, +/- 5%, 100 mW, -55 to 155 degC, 0402 (1005 Metric), RoHS, Tape and Reel")
      (fields (field (name "TOLERANCE") "5%") (field (name "MANUFACTURER") "Basic Passives"))
      (libsource (lib "MiniPC DB") (part "RES-0.05"))
    )
    (comp (ref "R25")
      (value "ERJ-2GE0R00X")
      (footprint "RESC1005X40X25LL05T05")
      (description "Chip Resistor, 0 mOhm, +/- 5%, 100 mW, -55 to 155 degC, 0402 (1005 Metric), RoHS, Tape and Reel")
      (fields (field (name "TOLERANCE") "5%") (field (name "MANUFACTURER") "Basic Passives"))
      (libsource (lib "MiniPC DB") (part "RES-0.05"))
    )
  )
  (nets
    (net (code "1") (name "/1V0") (class "Default")
      (node (ref "C230") (pin "1") (pinfunction "1_1") (pintype "passive"))
      (node (ref "C232") (pin "2") (pinfunction "2_2") (pintype "passive"))
      (node (ref "C233") (pin "2") (pinfunction "2_2") (pintype "passive"))
      (node (ref "C238") (pin "2") (pinfunction "2_2") (pintype "passive"))
      (node (ref "C239") (pin "2") (pinfunction "2_2") (pintype "passive"))
      (node (ref "C244") (pin "2") (pinfunction "2_2") (pintype "passive"))
      (node (ref "C245") (pin "2") (pinfunction "2_2") (pintype "passive"))
      (node (ref "C250") (pin "2") (pinfunction "2_2") (pintype "passive"))
      (node (ref "C251") (pin "2") (pinfunction "2_2") (pintype "passive"))
      (node (ref "C255") (pin "2") (pinfunction "2_2") (pintype "passive"))
      (node (ref "C256") (pin "2") (pinfunction "2_2") (pintype "passive"))
      (node (ref "C260") (pin "2") (pinfunction "2_2") (pintype "passive"))
      (node (ref "C261") (pin "2") (pinfunction "2_2") (pintype "passive"))
      (node (ref "C265") (pin "2") (pinfunction "2_2") (pintype "passive"))
      (node (ref "C266") (pin "2") (pinfunction "2_2") (pintype "passive"))
      (node (ref "C270") (pin "2") (pinfunction "2_2") (pintype "passive"))
      (node (ref "C271") (pin "2") (pinfunction "2_2") (pintype "passive"))
      (node (ref "C275") (pin "2") (pinfunction "2_2") (pintype "passive"))
      (node (ref "C276") (pin "2") (pinfunction "2_2") (pintype "passive"))
      (node (ref "C280") (pin "2") (pinfunction "2_2") (pintype "passive"))
      (node (ref "C281") (pin "2") (pinfunction "2_2") (pintype "passive"))
      (node (ref "C285") (pin "2") (pinfunction "2_2") (pintype "passive"))
      (node (ref "C286") (pin "2") (pinfunction "2_2") (pintype "passive"))
      (node (ref "C290") (pin "2") (pinfunction "2_2") (pintype "passive"))
      (node (ref "C291") (pin "2") (pinfunction "2_2") (pintype "passive"))
      (node (ref "C295") (pin "2") (pinfunction "2_2") (pintype "passive"))
      (node (ref "C296") (pin "2") (pinfunction "2_2") (pintype "passive"))
      (node (ref "C300") (pin "2") (pinfunction "2_2") (pintype "passive"))
      (node (ref "C301") (pin "2") (pinfunction "2_2") (pintype "passive"))
      (node (ref "C304") (pin "2") (pinfunction "2_2") (pintype "passive"))
      (node (ref "C305") (pin "2") (pinfunction "2_2") (pintype "passive"))
      (node (ref "C308") (pin "2") (pinfunction "2_2") (pintype "passive"))
      (node (ref "C309") (pin "2") (pinfunction "2_2") (pintype "passive"))
    )
    (net (code "2") (name "/DDR4VCC") (class "Default")
      (node (ref "C236") (pin "2") (pinfunction "2_2") (pintype "passive"))
      (node (ref "C242") (pin "2") (pinfunction "2_2") (pintype "passive"))
      (node (ref "C248") (pin "2") (pinfunction "2_2") (pintype "passive"))
      (node (ref "C253") (pin "2") (pinfunction "2_2") (pintype "passive"))
      (node (ref "C258") (pin "2") (pinfunction "2_2") (pintype "passive"))
      (node (ref "C263") (pin "2") (pinfunction "2_2") (pintype "passive"))
      (node (ref "C268") (pin "2") (pinfunction "2_2") (pintype "passive"))
      (node (ref "C273") (pin "2") (pinfunction "2_2") (pintype "passive"))
      (node (ref "C278") (pin "2") (pinfunction "2_2") (pintype "passive"))
      (node (ref "C283") (pin "2") (pinfunction "2_2") (pintype "passive"))
      (node (ref "C288") (pin "2") (pinfunction "2_2") (pintype "passive"))
      (node (ref "C293") (pin "2") (pinfunction "2_2") (pintype "passive"))
      (node (ref "C298") (pin "2") (pinfunction "2_2") (pintype "passive"))
      (node (ref "C303") (pin "2") (pinfunction "2_2") (pintype "passive"))
      (node (ref "C307") (pin "2") (pinfunction "2_2") (pintype "passive"))
    )
    (net (code "3") (name "/IO_1V8") (class "Default")
      (node (ref "C237") (pin "2") (pinfunction "2_2") (pintype "passive"))
      (node (ref "C243") (pin "2") (pinfunction "2_2") (pintype "passive"))
      (node (ref "C249") (pin "2") (pinfunction "2_2") (pintype "passive"))
      (node (ref "C254") (pin "2") (pinfunction "2_2") (pintype "passive"))
      (node (ref "C259") (pin "2") (pinfunction "2_2") (pintype "passive"))
      (node (ref "C264") (pin "2") (pinfunction "2_2") (pintype "passive"))
      (node (ref "C269") (pin "2") (pinfunction "2_2") (pintype "passive"))
      (node (ref "C274") (pin "2") (pinfunction "2_2") (pintype "passive"))
      (node (ref "C279") (pin "2") (pinfunction "2_2") (pintype "passive"))
      (node (ref "C284") (pin "2") (pinfunction "2_2") (pintype "passive"))
      (node (ref "C289") (pin "2") (pinfunction "2_2") (pintype "passive"))
      (node (ref "C294") (pin "2") (pinfunction "2_2") (pintype "passive"))
      (node (ref "C299") (pin "2") (pinfunction "2_2") (pintype "passive"))
      (node (ref "R24") (pin "1") (pinfunction "1_1") (pintype "passive"))
    )
    (net (code "4") (name "/PLL_1V8") (class "Default")
      (node (ref "C231") (pin "2") (pinfunction "2_2") (pintype "passive"))
      (node (ref "C234") (pin "2") (pinfunction "2_2") (pintype "passive"))
      (node (ref "C240") (pin "2") (pinfunction "2_2") (pintype "passive"))
      (node (ref "C246") (pin "2") (pinfunction "2_2") (pintype "passive"))
      (node (ref "C252") (pin "2") (pinfunction "2_2") (pintype "passive"))
      (node (ref "C257") (pin "2") (pinfunction "2_2") (pintype "passive"))
      (node (ref "C262") (pin "2") (pinfunction "2_2") (pintype "passive"))
      (node (ref "C267") (pin "2") (pinfunction "2_2") (pintype "passive"))
      (node (ref "C272") (pin "2") (pinfunction "2_2") (pintype "passive"))
      (node (ref "C277") (pin "2") (pinfunction "2_2") (pintype "passive"))
      (node (ref "C282") (pin "2") (pinfunction "2_2") (pintype "passive"))
      (node (ref "C287") (pin "2") (pinfunction "2_2") (pintype "passive"))
      (node (ref "C292") (pin "2") (pinfunction "2_2") (pintype "passive"))
      (node (ref "C297") (pin "2") (pinfunction "2_2") (pintype "passive"))
      (node (ref "C302") (pin "2") (pinfunction "2_2") (pintype "passive"))
      (node (ref "C306") (pin "2") (pinfunction "2_2") (pintype "passive"))
      (node (ref "C310") (pin "2") (pinfunction "2_2") (pintype "passive"))
      (node (ref "C312") (pin "2") (pinfunction "2_2") (pintype "passive"))
      (node (ref "C313") (pin "2") (pinfunction "2_2") (pintype "passive"))
      (node (ref "C314") (pin "2") (pinfunction "2_2") (pintype "passive"))
      (node (ref "C315") (pin "2") (pinfunction "2_2") (pintype "passive"))
      (node (ref "C320") (pin "2") (pinfunction "2_2") (pintype "passive"))
      (node (ref "L7") (pin "1") (pinfunction "1_1") (pintype "passive"))
      (node (ref "L8") (pin "1") (pinfunction "1_1") (pintype "passive"))
      (node (ref "R25") (pin "1") (pinfunction "1_1") (pintype "passive"))
    )
    (net (code "5") (name "/VADJ") (class "Default")
      (node (ref "C235") (pin "2") (pinfunction "2_2") (pintype "passive"))
      (node (ref "C241") (pin "2") (pinfunction "2_2") (pintype "passive"))
      (node (ref "C247") (pin "2") (pinfunction "2_2") (pintype "passive"))
    )
    (net (code "6") (name "/VCC_APLL") (class "Default")
      (node (ref "C316") (pin "2") (pinfunction "2_2") (pintype "passive"))
      (node (ref "C319") (pin "2") (pinfunction "2_2") (pintype "passive"))
      (node (ref "L7") (pin "2") (pinfunction "2_2") (pintype "passive"))
    )
    (net (code "7") (name "/VCC_APLL_HPS") (class "Default")
      (node (ref "C317") (pin "2") (pinfunction "2_2") (pintype "passive"))
      (node (ref "L8") (pin "2") (pinfunction "2_2") (pintype "passive"))
    )
    (net (code "8") (name "/VCC_IOREF_HPS") (class "Default")
      (node (ref "C318") (pin "2") (pinfunction "2_2") (pintype "passive"))
      (node (ref "R25") (pin "2") (pinfunction "2_2") (pintype "passive"))
    )
    (net (code "9") (name "/VCC_IO_HPS") (class "Default")
      (node (ref "C311") (pin "2") (pinfunction "2_2") (pintype "passive"))
      (node (ref "R24") (pin "2") (pinfunction "2_2") (pintype "passive"))
    )
    (net (code "10") (name "GND") (class "Default")
      (node (ref "C230") (pin "2") (pinfunction "2_2") (pintype "passive"))
      (node (ref "C231") (pin "1") (pinfunction "1_1") (pintype "passive"))
      (node (ref "C232") (pin "1") (pinfunction "1_1") (pintype "passive"))
      (node (ref "C233") (pin "1") (pinfunction "1_1") (pintype "passive"))
      (node (ref "C234") (pin "1") (pinfunction "1_1") (pintype "passive"))
      (node (ref "C235") (pin "1") (pinfunction "1_1") (pintype "passive"))
      (node (ref "C236") (pin "1") (pinfunction "1_1") (pintype "passive"))
      (node (ref "C237") (pin "1") (pinfunction "1_1") (pintype "passive"))
      (node (ref "C238") (pin "1") (pinfunction "1_1") (pintype "passive"))
      (node (ref "C239") (pin "1") (pinfunction "1_1") (pintype "passive"))
      (node (ref "C240") (pin "1") (pinfunction "1_1") (pintype "passive"))
      (node (ref "C241") (pin "1") (pinfunction "1_1") (pintype "passive"))
      (node (ref "C242") (pin "1") (pinfunction "1_1") (pintype "passive"))
      (node (ref "C243") (pin "1") (pinfunction "1_1") (pintype "passive"))
      (node (ref "C244") (pin "1") (pinfunction "1_1") (pintype "passive"))
      (node (ref "C245") (pin "1") (pinfunction "1_1") (pintype "passive"))
      (node (ref "C246") (pin "1") (pinfunction "1_1") (pintype "passive"))
      (node (ref "C247") (pin "1") (pinfunction "1_1") (pintype "passive"))
      (node (ref "C248") (pin "1") (pinfunction "1_1") (pintype "passive"))
      (node (ref "C249") (pin "1") (pinfunction "1_1") (pintype "passive"))
      (node (ref "C250") (pin "1") (pinfunction "1_1") (pintype "passive"))
      (node (ref "C251") (pin "1") (pinfunction "1_1") (pintype "passive"))
      (node (ref "C252") (pin "1") (pinfunction "1_1") (pintype "passive"))
      (node (ref "C253") (pin "1") (pinfunction "1_1") (pintype "passive"))
      (node (ref "C254") (pin "1") (pinfunction "1_1") (pintype "passive"))
      (node (ref "C255") (pin "1") (pinfunction "1_1") (pintype "passive"))
      (node (ref "C256") (pin "1") (pinfunction "1_1") (pintype "passive"))
      (node (ref "C257") (pin "1") (pinfunction "1_1") (pintype "passive"))
      (node (ref "C258") (pin "1") (pinfunction "1_1") (pintype "passive"))
      (node (ref "C259") (pin "1") (pinfunction "1_1") (pintype "passive"))
      (node (ref "C260") (pin "1") (pinfunction "1_1") (pintype "passive"))
      (node (ref "C261") (pin "1") (pinfunction "1_1") (pintype "passive"))
      (node (ref "C262") (pin "1") (pinfunction "1_1") (pintype "passive"))
      (node (ref "C263") (pin "1") (pinfunction "1_1") (pintype "passive"))
      (node (ref "C264") (pin "1") (pinfunction "1_1") (pintype "passive"))
      (node (ref "C265") (pin "1") (pinfunction "1_1") (pintype "passive"))
      (node (ref "C266") (pin "1") (pinfunction "1_1") (pintype "passive"))
      (node (ref "C267") (pin "1") (pinfunction "1_1") (pintype "passive"))
      (node (ref "C268") (pin "1") (pinfunction "1_1") (pintype "passive"))
      (node (ref "C269") (pin "1") (pinfunction "1_1") (pintype "passive"))
      (node (ref "C270") (pin "1") (pinfunction "1_1") (pintype "passive"))
      (node (ref "C271") (pin "1") (pinfunction "1_1") (pintype "passive"))
      (node (ref "C272") (pin "1") (pinfunction "1_1") (pintype "passive"))
      (node (ref "C273") (pin "1") (pinfunction "1_1") (pintype "passive"))
      (node (ref "C274") (pin "1") (pinfunction "1_1") (pintype "passive"))
      (node (ref "C275") (pin "1") (pinfunction "1_1") (pintype "passive"))
      (node (ref "C276") (pin "1") (pinfunction "1_1") (pintype "passive"))
      (node (ref "C277") (pin "1") (pinfunction "1_1") (pintype "passive"))
      (node (ref "C278") (pin "1") (pinfunction "1_1") (pintype "passive"))
      (node (ref "C279") (pin "1") (pinfunction "1_1") (pintype "passive"))
      (node (ref "C280") (pin "1") (pinfunction "1_1") (pintype "passive"))
      (node (ref "C281") (pin "1") (pinfunction "1_1") (pintype "passive"))
      (node (ref "C282") (pin "1") (pinfunction "1_1") (pintype "passive"))
      (node (ref "C283") (pin "1") (pinfunction "1_1") (pintype "passive"))
      (node (ref "C284") (pin "1") (pinfunction "1_1") (pintype "passive"))
      (node (ref "C285") (pin "1") (pinfunction "1_1") (pintype "passive"))
      (node (ref "C286") (pin "1") (pinfunction "1_1") (pintype "passive"))
      (node (ref "C287") (pin "1") (pinfunction "1_1") (pintype "passive"))
      (node (ref "C288") (pin "1") (pinfunction "1_1") (pintype "passive"))
      (node (ref "C289") (pin "1") (pinfunction "1_1") (pintype "passive"))
      (node (ref "C290") (pin "1") (pinfunction "1_1") (pintype "passive"))
      (node (ref "C291") (pin "1") (pinfunction "1_1") (pintype "passive"))
      (node (ref "C292") (pin "1") (pinfunction "1_1") (pintype "passive"))
      (node (ref "C293") (pin "1") (pinfunction "1_1") (pintype "passive"))
      (node (ref "C294") (pin "1") (pinfunction "1_1") (pintype "passive"))
      (node (ref "C295") (pin "1") (pinfunction "1_1") (pintype "passive"))
      (node (ref "C296") (pin "1") (pinfunction "1_1") (pintype "passive"))
      (node (ref "C297") (pin "1") (pinfunction "1_1") (pintype "passive"))
      (node (ref "C298") (pin "1") (pinfunction "1_1") (pintype "passive"))
      (node (ref "C299") (pin "1") (pinfunction "1_1") (pintype "passive"))
      (node (ref "C300") (pin "1") (pinfunction "1_1") (pintype "passive"))
      (node (ref "C301") (pin "1") (pinfunction "1_1") (pintype "passive"))
      (node (ref "C302") (pin "1") (pinfunction "1_1") (pintype "passive"))
      (node (ref "C303") (pin "1") (pinfunction "1_1") (pintype "passive"))
      (node (ref "C304") (pin "1") (pinfunction "1_1") (pintype "passive"))
      (node (ref "C305") (pin "1") (pinfunction "1_1") (pintype "passive"))
      (node (ref "C306") (pin "1") (pinfunction "1_1") (pintype "passive"))
      (node (ref "C307") (pin "1") (pinfunction "1_1") (pintype "passive"))
      (node (ref "C308") (pin "1") (pinfunction "1_1") (pintype "passive"))
      (node (ref "C309") (pin "1") (pinfunction "1_1") (pintype "passive"))
      (node (ref "C310") (pin "1") (pinfunction "1_1") (pintype "passive"))
      (node (ref "C311") (pin "1") (pinfunction "1_1") (pintype "passive"))
      (node (ref "C312") (pin "1") (pinfunction "1_1") (pintype "passive"))
      (node (ref "C313") (pin "1") (pinfunction "1_1") (pintype "passive"))
      (node (ref "C314") (pin "1") (pinfunction "1_1") (pintype "passive"))
      (node (ref "C315") (pin "1") (pinfunction "1_1") (pintype "passive"))
      (node (ref "C316") (pin "1") (pinfunction "1_1") (pintype "passive"))
      (node (ref "C317") (pin "1") (pinfunction "1_1") (pintype "passive"))
      (node (ref "C318") (pin "1") (pinfunction "1_1") (pintype "passive"))
      (node (ref "C319") (pin "1") (pinfunction "1_1") (pintype "passive"))
      (node (ref "C320") (pin "1") (pinfunction "1_1") (pintype "passive"))
    )
  )
)
